# I_O.net
KiCad netlist of a schematic drawn in Altium Designer
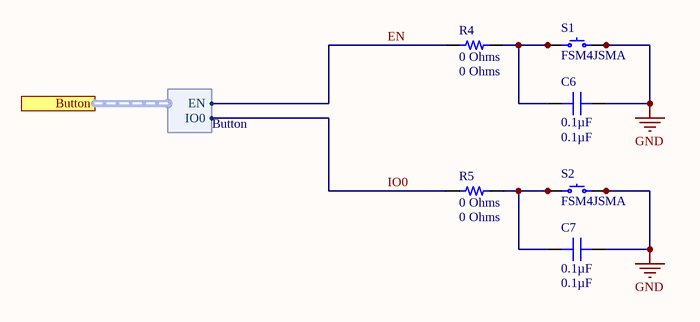
[diagram p0: I_O.SchDoc]

(export (version "E")
  (design (tool "Eeschema 10.0.6"))
  (components
    (comp (ref "C6")
      (value "0.1µF")
      (footprint "CAP 0805_2012")
      (description "CAP CER 0.1UF 10V X5R 0805")
      (fields (field (name "PART NUMBER") "0805ZD104KAT2A") (field (name "ALTIUM_VALUE") "0.1µF"))
      (libsource (lib "Celestial Altium Library - altium_library") (part "Capacitor"))
    )
    (comp (ref "C7")
      (value "0.1µF")
      (footprint "CAP 0805_2012")
      (description "CAP CER 0.1UF 10V X5R 0805")
      (fields (field (name "PART NUMBER") "0805ZD104KAT2A") (field (name "ALTIUM_VALUE") "0.1µF"))
      (libsource (lib "Celestial Altium Library - altium_library") (part "Capacitor"))
    )
    (comp (ref "R4")
      (value "0 Ohms")
      (footprint "RES 0805_2012")
      (description "RES 0 OHM JUMPER 1/8W 0805")
      (fields (field (name "PART NUMBER") "CRCW08050000Z0EBC") (field (name "ALTIUM_VALUE") "0 Ohms"))
      (libsource (lib "Celestial Altium Library - altium_library") (part "Resistor"))
    )
    (comp (ref "R5")
      (value "0 Ohms")
      (footprint "RES 0805_2012")
      (description "RES 0 OHM JUMPER 1/8W 0805")
      (fields (field (name "PART NUMBER") "CRCW08050000Z0EBC") (field (name "ALTIUM_VALUE") "0 Ohms"))
      (libsource (lib "Celestial Altium Library - altium_library") (part "Resistor"))
    )
    (comp (ref "S1")
      (value "FSM4JSMA")
      (footprint "TE FSM4JSMA")
      (description "SWITCH TACTILE SPST-NO 0.05A 24V")
      (fields (field (name "MANUFACTURER") "TE Connectivity ALCOSWITCH Switches"))
      (libsource (lib "Celestial Altium Library - altium_library") (part "SPST-NO 4 PIN"))
    )
    (comp (ref "S2")
      (value "FSM4JSMA")
      (footprint "TE FSM4JSMA")
      (description "SWITCH TACTILE SPST-NO 0.05A 24V")
      (fields (field (name "MANUFACTURER") "TE Connectivity ALCOSWITCH Switches"))
      (libsource (lib "Celestial Altium Library - altium_library") (part "SPST-NO 4 PIN"))
    )
  )
  (nets
    (net (code "2") (name "/EN") (class "Default")
      (node (ref "R4") (pin "1") (pinfunction "1_1") (pintype "passive"))
    )
    (net (code "3") (name "/IO0") (class "Default")
      (node (ref "R5") (pin "1") (pinfunction "1_1") (pintype "passive"))
    )
    (net (code "5") (name "GND") (class "Default")
      (node (ref "C6") (pin "1") (pinfunction "1_1") (pintype "passive"))
      (node (ref "C7") (pin "1") (pinfunction "1_1") (pintype "passive"))
      (node (ref "S1") (pin "3") (pinfunction "3_3") (pintype "passive"))
      (node (ref "S1") (pin "4") (pinfunction "4_4") (pintype "passive"))
      (node (ref "S2") (pin "3") (pinfunction "3_3") (pintype "passive"))
      (node (ref "S2") (pin "4") (pinfunction "4_4") (pintype "passive"))
    )
    (net (code "6") (name "Net-(C6-Pad2)") (class "Default")
      (node (ref "C6") (pin "2") (pinfunction "2_2") (pintype "passive"))
      (node (ref "R4") (pin "2") (pinfunction "2_2") (pintype "passive"))
      (node (ref "S1") (pin "1") (pinfunction "1_1") (pintype "passive"))
      (node (ref "S1") (pin "2") (pinfunction "2_2") (pintype "passive"))
    )
    (net (code "7") (name "Net-(C7-Pad2)") (class "Default")
      (node (ref "C7") (pin "2") (pinfunction "2_2") (pintype "passive"))
      (node (ref "R5") (pin "2") (pinfunction "2_2") (pintype "passive"))
      (node (ref "S2") (pin "1") (pinfunction "1_1") (pintype "passive"))
      (node (ref "S2") (pin "2") (pinfunction "2_2") (pintype "passive"))
    )
  )
)
